# R002A.net
KiCad netlist of a schematic drawn in EAGLE
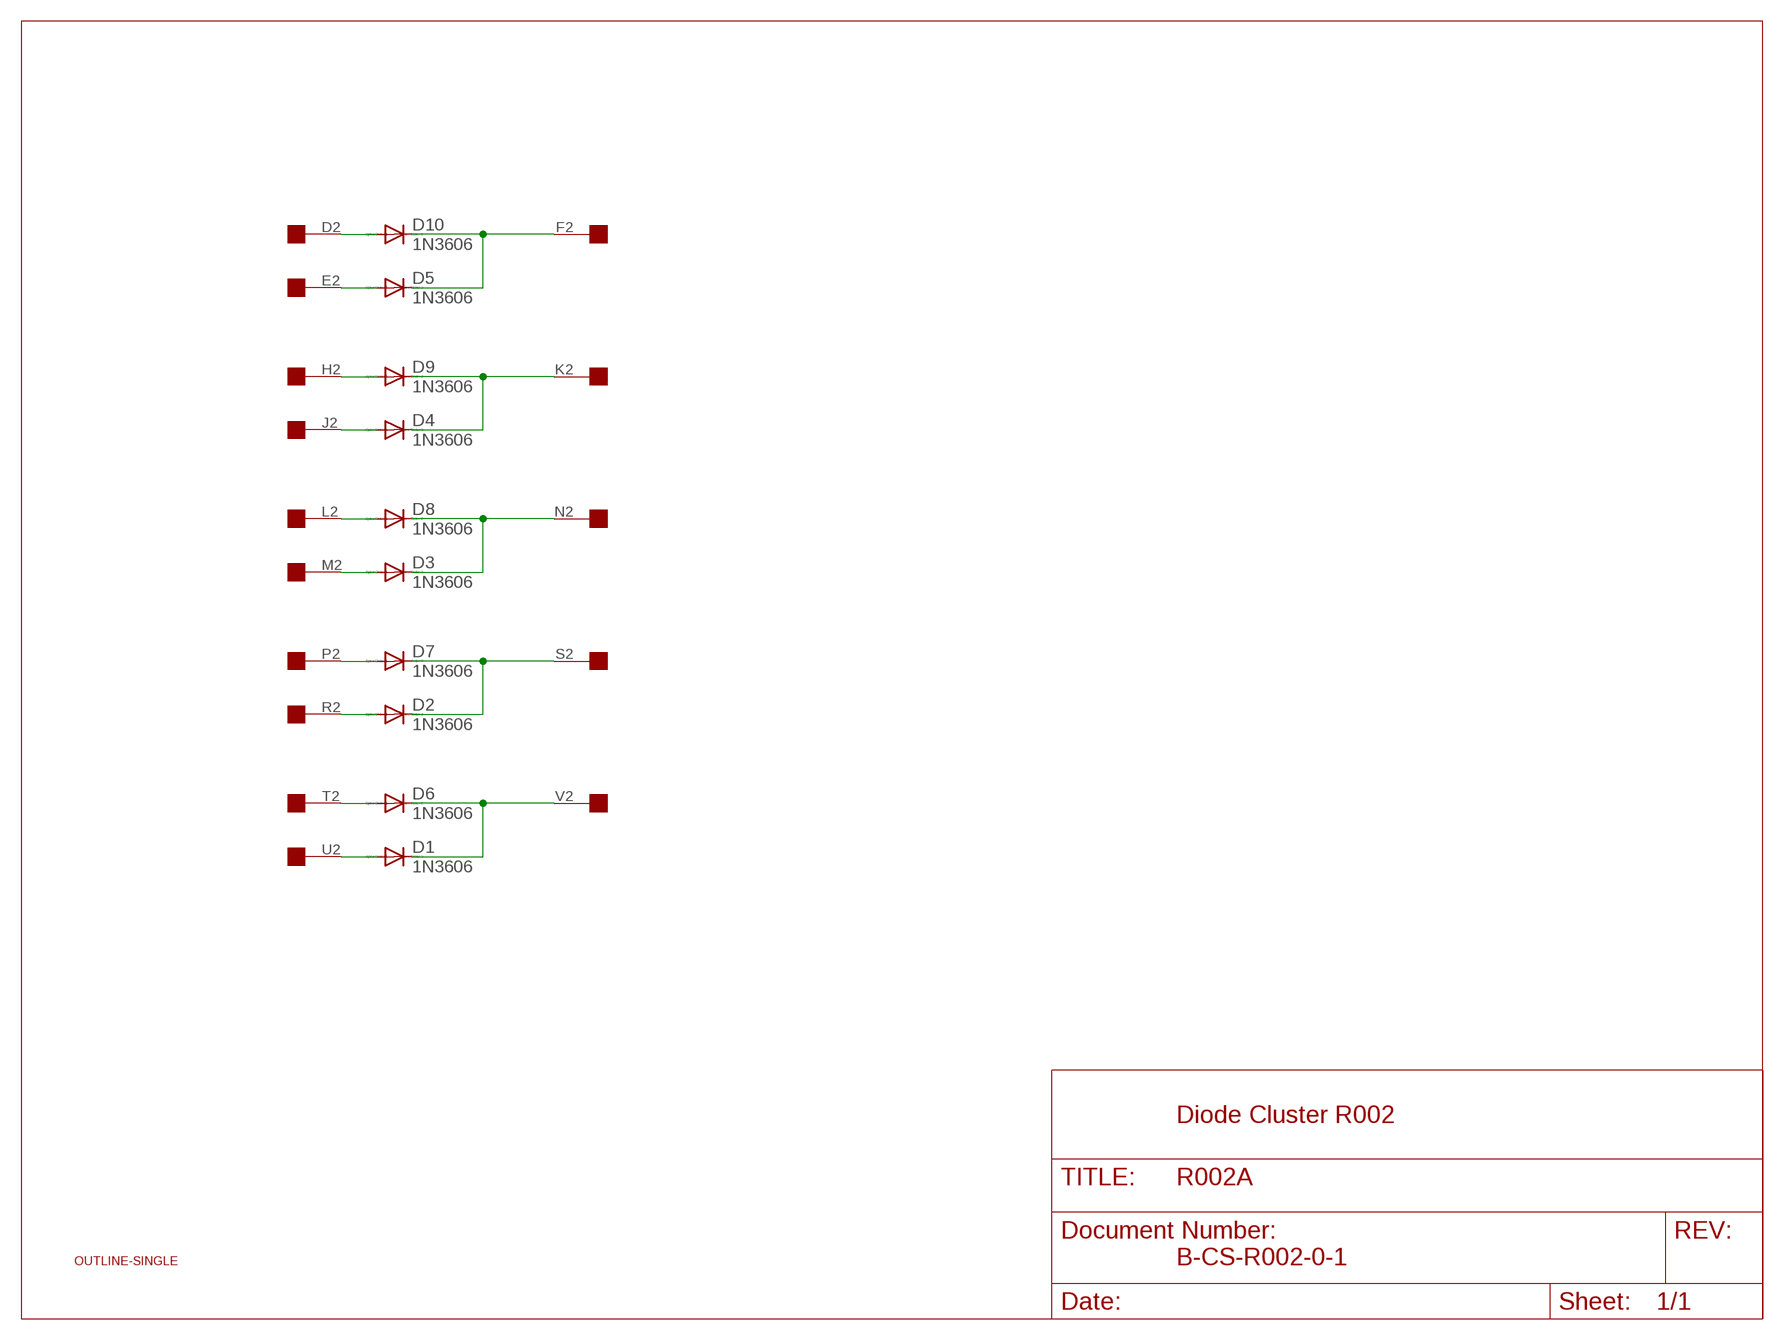
[diagram p0: schematic, sheet 1]

(export (version "E")
  (design (tool "Eeschema 10.0.6"))
  (components
    (comp (ref "D1")
      (value "1N3606")
      (footprint "eagle-import:DO35-10")
      (libsource (lib "eagle-import") (part "1N4148DO35-10"))
    )
    (comp (ref "D2")
      (value "1N3606")
      (footprint "eagle-import:DO35-10")
      (libsource (lib "eagle-import") (part "1N4148DO35-10"))
    )
    (comp (ref "D3")
      (value "1N3606")
      (footprint "eagle-import:DO35-10")
      (libsource (lib "eagle-import") (part "1N4148DO35-10"))
    )
    (comp (ref "D4")
      (value "1N3606")
      (footprint "eagle-import:DO35-10")
      (libsource (lib "eagle-import") (part "1N4148DO35-10"))
    )
    (comp (ref "D5")
      (value "1N3606")
      (footprint "eagle-import:DO35-10")
      (libsource (lib "eagle-import") (part "1N4148DO35-10"))
    )
    (comp (ref "D6")
      (value "1N3606")
      (footprint "eagle-import:DO35-10")
      (libsource (lib "eagle-import") (part "1N4148DO35-10"))
    )
    (comp (ref "D7")
      (value "1N3606")
      (footprint "eagle-import:DO35-10")
      (libsource (lib "eagle-import") (part "1N4148DO35-10"))
    )
    (comp (ref "D8")
      (value "1N3606")
      (footprint "eagle-import:DO35-10")
      (libsource (lib "eagle-import") (part "1N4148DO35-10"))
    )
    (comp (ref "D9")
      (value "1N3606")
      (footprint "eagle-import:DO35-10")
      (libsource (lib "eagle-import") (part "1N4148DO35-10"))
    )
    (comp (ref "D10")
      (value "1N3606")
      (footprint "eagle-import:DO35-10")
      (libsource (lib "eagle-import") (part "1N4148DO35-10"))
    )
    (comp (ref "U$1")
      (value "OUTLINE-SINGLE")
      (footprint "eagle-import:SINGLE")
      (libsource (lib "eagle-import") (part "OUTLINE-SINGLE"))
    )
    (comp (ref "U$2")
      (value "EDGE-1")
      (footprint "eagle-import:EDGE-CON1")
      (libsource (lib "eagle-import") (part "EDGE-1"))
    )
  )
  (nets
    (net (code "1") (name "Net-(U$2D-1)") (class "Default")
      (node (ref "D10") (pin "A") (pinfunction "A_A") (pintype "passive"))
      (node (ref "U$2") (pin "D2") (pinfunction "1_D2") (pintype "bidirectional"))
    )
    (net (code "2") (name "Net-(U$2E-1)") (class "Default")
      (node (ref "D5") (pin "A") (pinfunction "A_A") (pintype "passive"))
      (node (ref "U$2") (pin "E2") (pinfunction "1_E2") (pintype "bidirectional"))
    )
    (net (code "3") (name "Net-(U$2F-1)") (class "Default")
      (node (ref "D10") (pin "C") (pinfunction "C_C") (pintype "passive"))
      (node (ref "D5") (pin "C") (pinfunction "C_C") (pintype "passive"))
      (node (ref "U$2") (pin "F2") (pinfunction "1_F2") (pintype "bidirectional"))
    )
    (net (code "4") (name "Net-(U$2G-1)") (class "Default")
      (node (ref "D9") (pin "A") (pinfunction "A_A") (pintype "passive"))
      (node (ref "U$2") (pin "H2") (pinfunction "1_H2") (pintype "bidirectional"))
    )
    (net (code "5") (name "Net-(U$2H-1)") (class "Default")
      (node (ref "D4") (pin "A") (pinfunction "A_A") (pintype "passive"))
      (node (ref "U$2") (pin "J2") (pinfunction "1_J2") (pintype "bidirectional"))
    )
    (net (code "6") (name "Net-(U$2I-1)") (class "Default")
      (node (ref "D4") (pin "C") (pinfunction "C_C") (pintype "passive"))
      (node (ref "D9") (pin "C") (pinfunction "C_C") (pintype "passive"))
      (node (ref "U$2") (pin "K2") (pinfunction "1_K2") (pintype "bidirectional"))
    )
    (net (code "7") (name "Net-(U$2J-1)") (class "Default")
      (node (ref "D8") (pin "A") (pinfunction "A_A") (pintype "passive"))
      (node (ref "U$2") (pin "L2") (pinfunction "1_L2") (pintype "bidirectional"))
    )
    (net (code "8") (name "Net-(U$2K-1)") (class "Default")
      (node (ref "D3") (pin "A") (pinfunction "A_A") (pintype "passive"))
      (node (ref "U$2") (pin "M2") (pinfunction "1_M2") (pintype "bidirectional"))
    )
    (net (code "9") (name "Net-(U$2L-1)") (class "Default")
      (node (ref "D3") (pin "C") (pinfunction "C_C") (pintype "passive"))
      (node (ref "D8") (pin "C") (pinfunction "C_C") (pintype "passive"))
      (node (ref "U$2") (pin "N2") (pinfunction "1_N2") (pintype "bidirectional"))
    )
    (net (code "10") (name "Net-(U$2M-1)") (class "Default")
      (node (ref "D7") (pin "A") (pinfunction "A_A") (pintype "passive"))
      (node (ref "U$2") (pin "P2") (pinfunction "1_P2") (pintype "bidirectional"))
    )
    (net (code "11") (name "Net-(U$2N-1)") (class "Default")
      (node (ref "D2") (pin "A") (pinfunction "A_A") (pintype "passive"))
      (node (ref "U$2") (pin "R2") (pinfunction "1_R2") (pintype "bidirectional"))
    )
    (net (code "12") (name "Net-(U$2O-1)") (class "Default")
      (node (ref "D2") (pin "C") (pinfunction "C_C") (pintype "passive"))
      (node (ref "D7") (pin "C") (pinfunction "C_C") (pintype "passive"))
      (node (ref "U$2") (pin "S2") (pinfunction "1_S2") (pintype "bidirectional"))
    )
    (net (code "13") (name "Net-(U$2P-1)") (class "Default")
      (node (ref "D6") (pin "A") (pinfunction "A_A") (pintype "passive"))
      (node (ref "U$2") (pin "T2") (pinfunction "1_T2") (pintype "bidirectional"))
    )
    (net (code "14") (name "Net-(U$2Q-1)") (class "Default")
      (node (ref "D1") (pin "A") (pinfunction "A_A") (pintype "passive"))
      (node (ref "U$2") (pin "U2") (pinfunction "1_U2") (pintype "bidirectional"))
    )
    (net (code "15") (name "Net-(U$2R-1)") (class "Default")
      (node (ref "D1") (pin "C") (pinfunction "C_C") (pintype "passive"))
      (node (ref "D6") (pin "C") (pinfunction "C_C") (pintype "passive"))
      (node (ref "U$2") (pin "V2") (pinfunction "1_V2") (pintype "bidirectional"))
    )
  )
)
